# solderstation_v1_7sch.net
KiCad netlist of a schematic drawn in EAGLE
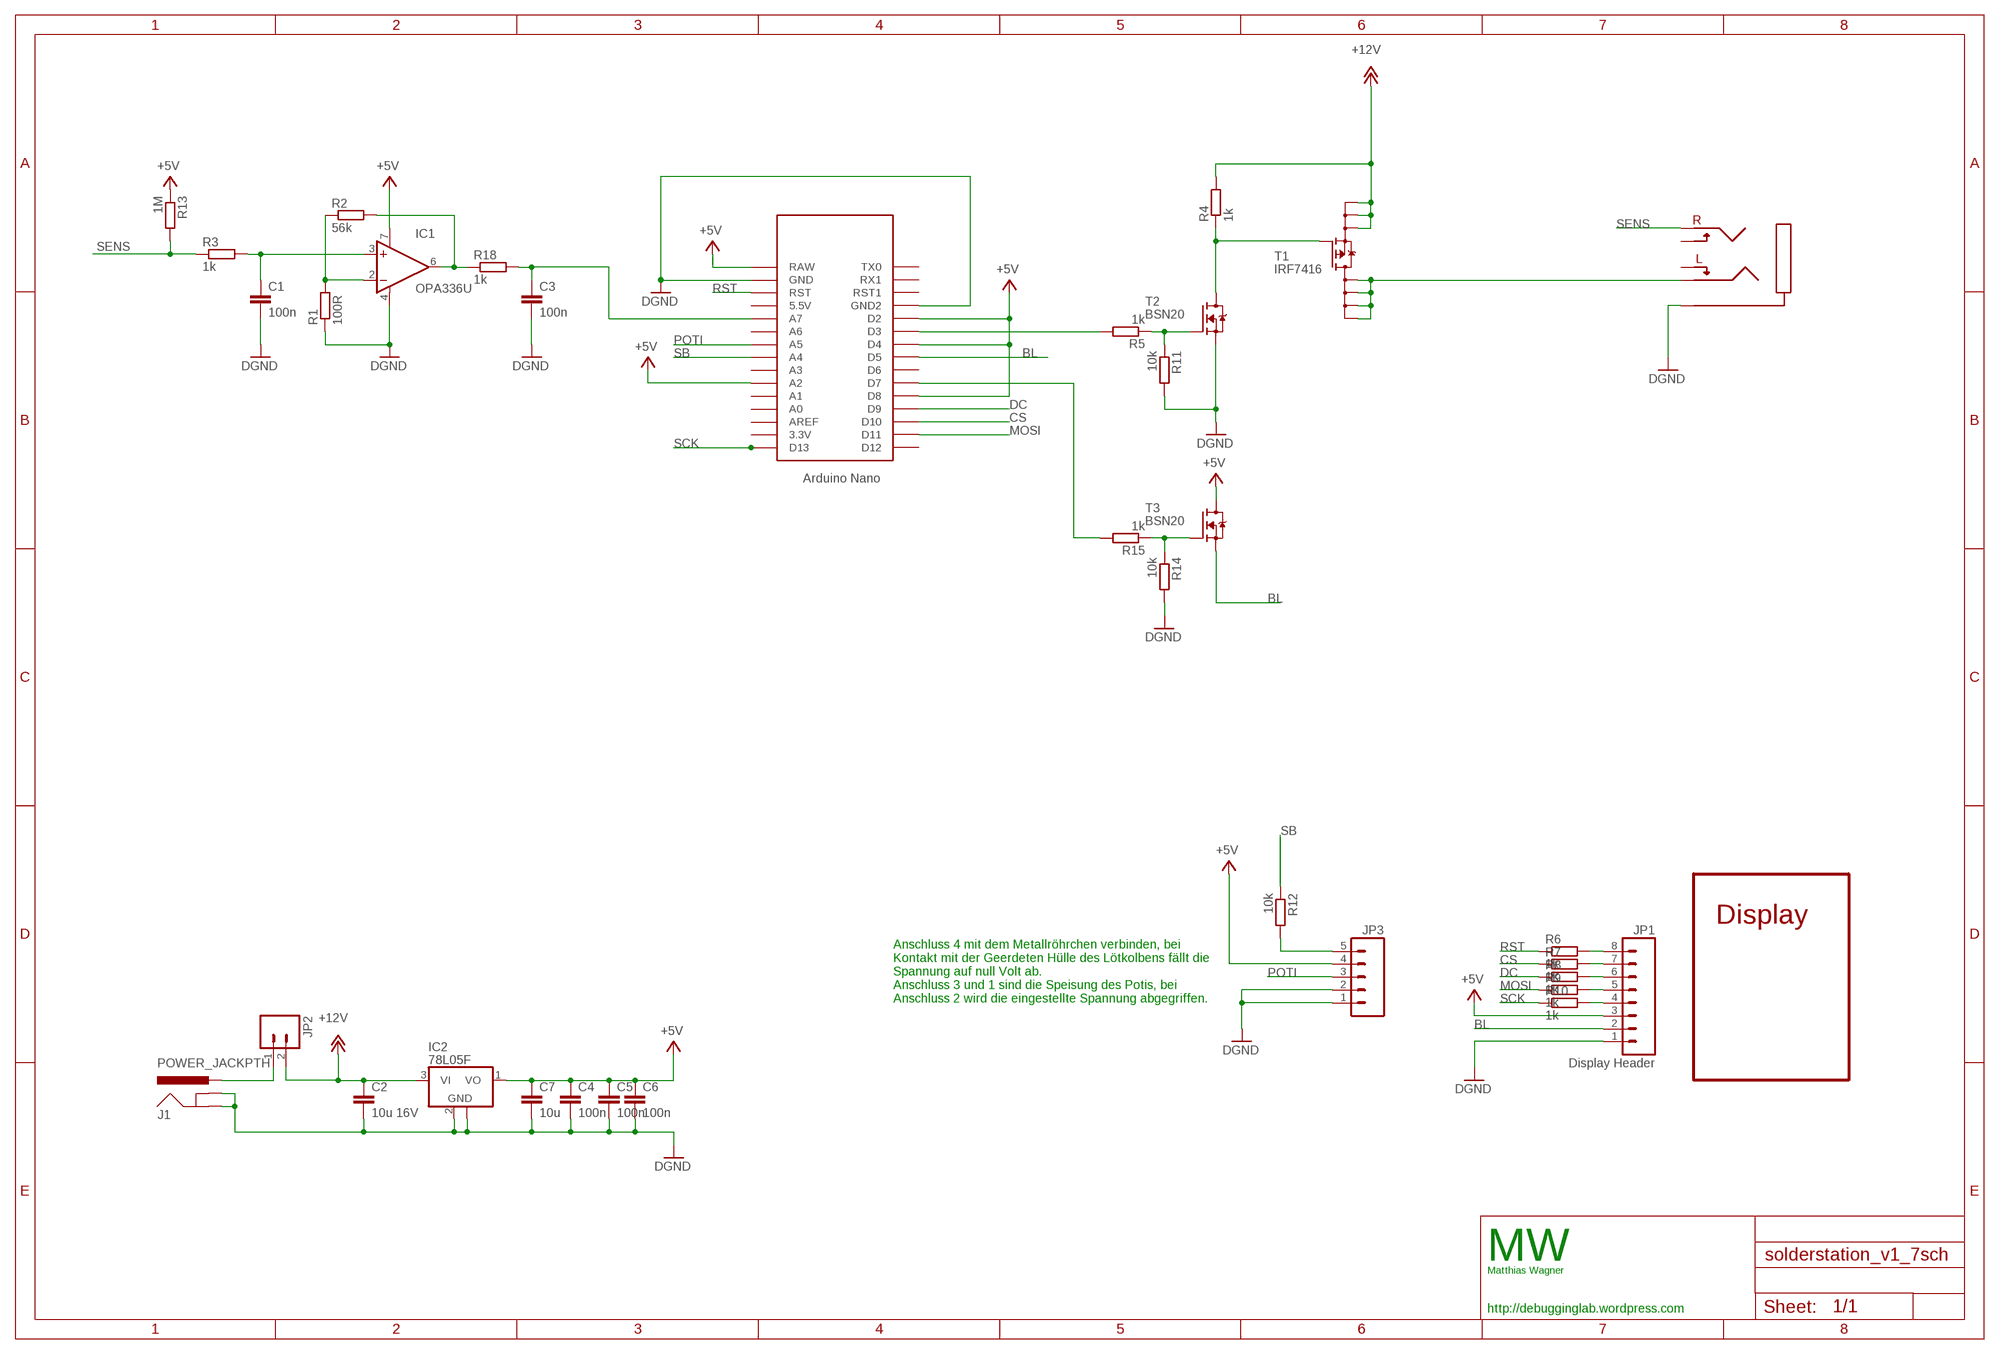
[diagram p0: schematic, sheet 1]

(export (version "E")
  (design (tool "Eeschema 10.0.6"))
  (components
    (comp (ref "C1")
      (value "100n")
      (footprint "eagle-import:C0603")
      (libsource (lib "eagle-import") (part "C-EUC0603"))
    )
    (comp (ref "C2")
      (value "10u 16V")
      (footprint "eagle-import:C1206")
      (libsource (lib "eagle-import") (part "C-EUC1206"))
    )
    (comp (ref "C3")
      (value "100n")
      (footprint "eagle-import:C0603")
      (libsource (lib "eagle-import") (part "C-EUC0603"))
    )
    (comp (ref "C4")
      (value "100n")
      (footprint "eagle-import:C0603")
      (libsource (lib "eagle-import") (part "C-EUC0603"))
    )
    (comp (ref "C5")
      (value "100n")
      (footprint "eagle-import:C0603")
      (libsource (lib "eagle-import") (part "C-EUC0603"))
    )
    (comp (ref "C6")
      (value "100n")
      (footprint "eagle-import:C0603")
      (libsource (lib "eagle-import") (part "C-EUC0603"))
    )
    (comp (ref "C7")
      (value "10u")
      (footprint "eagle-import:C1206")
      (libsource (lib "eagle-import") (part "C-EUC1206"))
    )
    (comp (ref "IC1")
      (value "OPA336U")
      (footprint "eagle-import:SO08")
      (fields (field (name "MF") "TEXAS INSTRUMENT CONNECTORS") (field (name "MPN") "OPA336UA"))
      (libsource (lib "eagle-import") (part "OPA336U"))
    )
    (comp (ref "IC2")
      (value "78L05F")
      (footprint "eagle-import:SOT89")
      (libsource (lib "eagle-import") (part "78LF05"))
    )
    (comp (ref "J1")
      (value "POWER_JACKPTH")
      (footprint "eagle-import:POWER_JACK_PTH")
      (libsource (lib "eagle-import") (part "POWER_JACKPTH"))
    )
    (comp (ref "JP1")
      (value "Display Header")
      (footprint "eagle-import:1X08_LOCK")
      (libsource (lib "eagle-import") (part "M08LOCK"))
    )
    (comp (ref "JP2")
      (value "M02LOCK_LONGPADS")
      (footprint "eagle-import:1X02_LOCK_LONGPADS")
      (libsource (lib "eagle-import") (part "M02LOCK_LONGPADS"))
    )
    (comp (ref "JP3")
      (value "M05")
      (footprint "eagle-import:05P")
      (libsource (lib "eagle-import") (part "M05"))
    )
    (comp (ref "R1")
      (value "100R")
      (footprint "eagle-import:R0603")
      (libsource (lib "eagle-import") (part "R-EU_R0603"))
    )
    (comp (ref "R2")
      (value "56k")
      (footprint "eagle-import:R0603")
      (libsource (lib "eagle-import") (part "R-EU_R0603"))
    )
    (comp (ref "R3")
      (value "1k")
      (footprint "eagle-import:R0603")
      (libsource (lib "eagle-import") (part "R-EU_R0603"))
    )
    (comp (ref "R4")
      (value "1k")
      (footprint "eagle-import:R0603")
      (libsource (lib "eagle-import") (part "R-EU_R0603"))
    )
    (comp (ref "R5")
      (value "1k")
      (footprint "eagle-import:R0603")
      (libsource (lib "eagle-import") (part "R-EU_R0603"))
    )
    (comp (ref "R6")
      (value "1k")
      (footprint "eagle-import:R0603")
      (libsource (lib "eagle-import") (part "R-EU_R0603"))
    )
    (comp (ref "R7")
      (value "1k")
      (footprint "eagle-import:R0603")
      (libsource (lib "eagle-import") (part "R-EU_R0603"))
    )
    (comp (ref "R8")
      (value "1k")
      (footprint "eagle-import:R0603")
      (libsource (lib "eagle-import") (part "R-EU_R0603"))
    )
    (comp (ref "R9")
      (value "1k")
      (footprint "eagle-import:R0603")
      (libsource (lib "eagle-import") (part "R-EU_R0603"))
    )
    (comp (ref "R10")
      (value "1k")
      (footprint "eagle-import:R0603")
      (libsource (lib "eagle-import") (part "R-EU_R0603"))
    )
    (comp (ref "R11")
      (value "10k")
      (footprint "eagle-import:R0603")
      (libsource (lib "eagle-import") (part "R-EU_R0603"))
    )
    (comp (ref "R12")
      (value "10k")
      (footprint "eagle-import:R0603")
      (libsource (lib "eagle-import") (part "R-EU_R0603"))
    )
    (comp (ref "R13")
      (value "1M")
      (footprint "eagle-import:R0603")
      (libsource (lib "eagle-import") (part "R-EU_R0603"))
    )
    (comp (ref "R14")
      (value "10k")
      (footprint "eagle-import:R0603")
      (libsource (lib "eagle-import") (part "R-EU_R0603"))
    )
    (comp (ref "R15")
      (value "1k")
      (footprint "eagle-import:R0603")
      (libsource (lib "eagle-import") (part "R-EU_R0603"))
    )
    (comp (ref "R18")
      (value "1k")
      (footprint "eagle-import:R0603")
      (libsource (lib "eagle-import") (part "R-EU_R0603"))
    )
    (comp (ref "T1")
      (value "IRF7416")
      (footprint "eagle-import:SO8")
      (libsource (lib "eagle-import") (part "IRF7416"))
    )
    (comp (ref "T2")
      (value "BSN20")
      (footprint "eagle-import:SOT23")
      (libsource (lib "eagle-import") (part "BSN20"))
    )
    (comp (ref "T3")
      (value "BSN20")
      (footprint "eagle-import:SOT23")
      (libsource (lib "eagle-import") (part "BSN20"))
    )
    (comp (ref "U$1")
      (value "NANO")
      (footprint "eagle-import:NANO")
      (libsource (lib "eagle-import") (part "NANO"))
    )
    (comp (ref "U$2")
      (value "AUDIO_JACK_3,5MMCONRAD")
      (footprint "eagle-import:AUDIO_JACK_3,5MM_CONRAD")
      (libsource (lib "eagle-import") (part "AUDIO_JACK_3,5MMCONRAD"))
    )
  )
  (nets
    (net (code "1") (name "+5V") (class "Default")
      (node (ref "C4") (pin "1") (pinfunction "1_1") (pintype "passive"))
      (node (ref "C5") (pin "1") (pinfunction "1_1") (pintype "passive"))
      (node (ref "C6") (pin "1") (pinfunction "1_1") (pintype "passive"))
      (node (ref "C7") (pin "1") (pinfunction "1_1") (pintype "passive"))
      (node (ref "IC1") (pin "7") (pinfunction "V+_7") (pintype "power_in"))
      (node (ref "IC2") (pin "1") (pinfunction "VO_1") (pintype "passive"))
      (node (ref "JP1") (pin "3") (pinfunction "3_3") (pintype "passive"))
      (node (ref "JP3") (pin "4") (pinfunction "4_4") (pintype "passive"))
      (node (ref "R13") (pin "1") (pinfunction "1_1") (pintype "passive"))
      (node (ref "T3") (pin "3") (pinfunction "D_3") (pintype "passive"))
      (node (ref "U$1") (pin "A2") (pinfunction "A2_A2") (pintype "bidirectional"))
      (node (ref "U$1") (pin "D2") (pinfunction "D2_D2") (pintype "bidirectional"))
      (node (ref "U$1") (pin "D4") (pinfunction "D4_D4") (pintype "bidirectional"))
      (node (ref "U$1") (pin "D8") (pinfunction "D8_D8") (pintype "bidirectional"))
      (node (ref "U$1") (pin "RAW") (pinfunction "RAW_RAW") (pintype "bidirectional"))
    )
    (net (code "2") (name "+12V") (class "Default")
      (node (ref "C2") (pin "1") (pinfunction "1_1") (pintype "passive"))
      (node (ref "IC2") (pin "3") (pinfunction "VI_3") (pintype "input"))
      (node (ref "JP2") (pin "2") (pinfunction "2_2") (pintype "passive"))
      (node (ref "R4") (pin "2") (pinfunction "2_2") (pintype "passive"))
      (node (ref "T1") (pin "1") (pinfunction "S0_1") (pintype "passive"))
      (node (ref "T1") (pin "2") (pinfunction "S1_2") (pintype "passive"))
      (node (ref "T1") (pin "3") (pinfunction "S2_3") (pintype "passive"))
    )
    (net (code "3") (name "/BL") (class "Default")
      (node (ref "JP1") (pin "2") (pinfunction "2_2") (pintype "passive"))
      (node (ref "T3") (pin "2") (pinfunction "S_2") (pintype "passive"))
      (node (ref "U$1") (pin "D5") (pinfunction "D5_D5") (pintype "bidirectional"))
    )
    (net (code "4") (name "/CS") (class "Default")
      (node (ref "R7") (pin "1") (pinfunction "1_1") (pintype "passive"))
      (node (ref "U$1") (pin "D10") (pinfunction "D10_D10") (pintype "bidirectional"))
    )
    (net (code "5") (name "/DC") (class "Default")
      (node (ref "R8") (pin "1") (pinfunction "1_1") (pintype "passive"))
      (node (ref "U$1") (pin "D9") (pinfunction "D9_D9") (pintype "bidirectional"))
    )
    (net (code "6") (name "/MOSI") (class "Default")
      (node (ref "R9") (pin "1") (pinfunction "1_1") (pintype "passive"))
      (node (ref "U$1") (pin "D11") (pinfunction "D11_D11") (pintype "bidirectional"))
    )
    (net (code "7") (name "/POTI") (class "Default")
      (node (ref "JP3") (pin "3") (pinfunction "3_3") (pintype "passive"))
      (node (ref "U$1") (pin "A5") (pinfunction "A5_A5") (pintype "bidirectional"))
    )
    (net (code "8") (name "/RST") (class "Default")
      (node (ref "R6") (pin "1") (pinfunction "1_1") (pintype "passive"))
      (node (ref "U$1") (pin "RST") (pinfunction "RST_RST") (pintype "bidirectional"))
    )
    (net (code "9") (name "/SB") (class "Default")
      (node (ref "R12") (pin "1") (pinfunction "1_1") (pintype "passive"))
      (node (ref "U$1") (pin "A4") (pinfunction "A4_A4") (pintype "bidirectional"))
    )
    (net (code "10") (name "/SCK") (class "Default")
      (node (ref "R10") (pin "1") (pinfunction "1_1") (pintype "passive"))
      (node (ref "U$1") (pin "D13") (pinfunction "D13_D13") (pintype "bidirectional"))
    )
    (net (code "11") (name "/SENS") (class "Default")
      (node (ref "R13") (pin "2") (pinfunction "2_2") (pintype "passive"))
      (node (ref "R3") (pin "1") (pinfunction "1_1") (pintype "passive"))
      (node (ref "U$2") (pin "P_RIGHT") (pinfunction "P$1_P_RIGHT") (pintype "bidirectional"))
    )
    (net (code "12") (name "DGND") (class "Default")
      (node (ref "C1") (pin "2") (pinfunction "2_2") (pintype "passive"))
      (node (ref "C2") (pin "2") (pinfunction "2_2") (pintype "passive"))
      (node (ref "C3") (pin "2") (pinfunction "2_2") (pintype "passive"))
      (node (ref "C4") (pin "2") (pinfunction "2_2") (pintype "passive"))
      (node (ref "C5") (pin "2") (pinfunction "2_2") (pintype "passive"))
      (node (ref "C6") (pin "2") (pinfunction "2_2") (pintype "passive"))
      (node (ref "C7") (pin "2") (pinfunction "2_2") (pintype "passive"))
      (node (ref "IC1") (pin "4") (pinfunction "V-_4") (pintype "power_in"))
      (node (ref "IC2") (pin "2") (pinfunction "GND_2") (pintype "passive"))
      (node (ref "IC2") (pin "2@1") (pinfunction "GND_2@1") (pintype "passive"))
      (node (ref "J1") (pin "GND") (pinfunction "GND_GND") (pintype "bidirectional"))
      (node (ref "J1") (pin "GNDBREAK") (pinfunction "GNDBREAK_GNDBREAK") (pintype "bidirectional"))
      (node (ref "JP1") (pin "1") (pinfunction "1_1") (pintype "passive"))
      (node (ref "JP3") (pin "1") (pinfunction "1_1") (pintype "passive"))
      (node (ref "JP3") (pin "2") (pinfunction "2_2") (pintype "passive"))
      (node (ref "R1") (pin "1") (pinfunction "1_1") (pintype "passive"))
      (node (ref "R11") (pin "2") (pinfunction "2_2") (pintype "passive"))
      (node (ref "R14") (pin "2") (pinfunction "2_2") (pintype "passive"))
      (node (ref "T2") (pin "2") (pinfunction "S_2") (pintype "passive"))
      (node (ref "U$1") (pin "GND") (pinfunction "GND_GND") (pintype "bidirectional"))
      (node (ref "U$1") (pin "GND1") (pinfunction "GND2_GND1") (pintype "bidirectional"))
      (node (ref "U$2") (pin "P_GND") (pinfunction "P$5_P_GND") (pintype "bidirectional"))
    )
    (net (code "13") (name "Net-(C3-Pad1)") (class "Default")
      (node (ref "C3") (pin "1") (pinfunction "1_1") (pintype "passive"))
      (node (ref "R18") (pin "2") (pinfunction "2_2") (pintype "passive"))
      (node (ref "U$1") (pin "A7") (pinfunction "A7_A7") (pintype "bidirectional"))
    )
    (net (code "14") (name "Net-(IC1-+IN)") (class "Default")
      (node (ref "C1") (pin "1") (pinfunction "1_1") (pintype "passive"))
      (node (ref "IC1") (pin "3") (pinfunction "+IN_3") (pintype "input"))
      (node (ref "R3") (pin "2") (pinfunction "2_2") (pintype "passive"))
    )
    (net (code "15") (name "Net-(IC1--IN)") (class "Default")
      (node (ref "IC1") (pin "2") (pinfunction "-IN_2") (pintype "input"))
      (node (ref "R1") (pin "2") (pinfunction "2_2") (pintype "passive"))
      (node (ref "R2") (pin "1") (pinfunction "1_1") (pintype "passive"))
    )
    (net (code "16") (name "Net-(IC1-OUT)") (class "Default")
      (node (ref "IC1") (pin "6") (pinfunction "OUT_6") (pintype "output"))
      (node (ref "R18") (pin "1") (pinfunction "1_1") (pintype "passive"))
      (node (ref "R2") (pin "2") (pinfunction "2_2") (pintype "passive"))
    )
    (net (code "17") (name "Net-(J1-PadPWR)") (class "Default")
      (node (ref "J1") (pin "PWR") (pinfunction "PWR_PWR") (pintype "bidirectional"))
      (node (ref "JP2") (pin "1") (pinfunction "1_1") (pintype "passive"))
    )
    (net (code "18") (name "Net-(JP1-Pad4)") (class "Default")
      (node (ref "JP1") (pin "4") (pinfunction "4_4") (pintype "passive"))
      (node (ref "R10") (pin "2") (pinfunction "2_2") (pintype "passive"))
    )
    (net (code "19") (name "Net-(JP1-Pad5)") (class "Default")
      (node (ref "JP1") (pin "5") (pinfunction "5_5") (pintype "passive"))
      (node (ref "R9") (pin "2") (pinfunction "2_2") (pintype "passive"))
    )
    (net (code "20") (name "Net-(JP1-Pad6)") (class "Default")
      (node (ref "JP1") (pin "6") (pinfunction "6_6") (pintype "passive"))
      (node (ref "R8") (pin "2") (pinfunction "2_2") (pintype "passive"))
    )
    (net (code "21") (name "Net-(JP1-Pad7)") (class "Default")
      (node (ref "JP1") (pin "7") (pinfunction "7_7") (pintype "passive"))
      (node (ref "R7") (pin "2") (pinfunction "2_2") (pintype "passive"))
    )
    (net (code "22") (name "Net-(JP1-Pad8)") (class "Default")
      (node (ref "JP1") (pin "8") (pinfunction "8_8") (pintype "passive"))
      (node (ref "R6") (pin "2") (pinfunction "2_2") (pintype "passive"))
    )
    (net (code "23") (name "Net-(JP3-Pad5)") (class "Default")
      (node (ref "JP3") (pin "5") (pinfunction "5_5") (pintype "passive"))
      (node (ref "R12") (pin "2") (pinfunction "2_2") (pintype "passive"))
    )
    (net (code "24") (name "Net-(R5-Pad2)") (class "Default")
      (node (ref "R5") (pin "2") (pinfunction "2_2") (pintype "passive"))
      (node (ref "U$1") (pin "D3") (pinfunction "D3_D3") (pintype "bidirectional"))
    )
    (net (code "25") (name "Net-(R15-Pad2)") (class "Default")
      (node (ref "R15") (pin "2") (pinfunction "2_2") (pintype "passive"))
      (node (ref "U$1") (pin "D7") (pinfunction "D7_D7") (pintype "bidirectional"))
    )
    (net (code "26") (name "Net-(T1-D0)") (class "Default")
      (node (ref "T1") (pin "5") (pinfunction "D0_5") (pintype "passive"))
      (node (ref "T1") (pin "6") (pinfunction "D1_6") (pintype "passive"))
      (node (ref "T1") (pin "7") (pinfunction "D2_7") (pintype "passive"))
      (node (ref "T1") (pin "8") (pinfunction "D3_8") (pintype "passive"))
      (node (ref "U$2") (pin "P_LEFT") (pinfunction "P$4_P_LEFT") (pintype "bidirectional"))
    )
    (net (code "27") (name "Net-(T1-G)") (class "Default")
      (node (ref "R4") (pin "1") (pinfunction "1_1") (pintype "passive"))
      (node (ref "T1") (pin "4") (pinfunction "G_4") (pintype "passive"))
      (node (ref "T2") (pin "3") (pinfunction "D_3") (pintype "passive"))
    )
    (net (code "28") (name "Net-(T2-G)") (class "Default")
      (node (ref "R11") (pin "1") (pinfunction "1_1") (pintype "passive"))
      (node (ref "R5") (pin "1") (pinfunction "1_1") (pintype "passive"))
      (node (ref "T2") (pin "1") (pinfunction "G_1") (pintype "passive"))
    )
    (net (code "29") (name "Net-(T3-G)") (class "Default")
      (node (ref "R14") (pin "1") (pinfunction "1_1") (pintype "passive"))
      (node (ref "R15") (pin "1") (pinfunction "1_1") (pintype "passive"))
      (node (ref "T3") (pin "1") (pinfunction "G_1") (pintype "passive"))
    )
    (net (code "30") (name "unconnected-(U$1-5.5V-Pad5V)") (class "Default")
      (node (ref "U$1") (pin "5V") (pinfunction "5.5V_5V") (pintype "bidirectional"))
    )
    (net (code "31") (name "unconnected-(U$1-Pad3.3V)") (class "Default")
      (node (ref "U$1") (pin "3.3V") (pinfunction "3.3V_3.3V") (pintype "bidirectional"))
    )
    (net (code "32") (name "unconnected-(U$1-PadA0)") (class "Default")
      (node (ref "U$1") (pin "A0") (pinfunction "A0_A0") (pintype "bidirectional"))
    )
    (net (code "33") (name "unconnected-(U$1-PadA1)") (class "Default")
      (node (ref "U$1") (pin "A1") (pinfunction "A1_A1") (pintype "bidirectional"))
    )
    (net (code "34") (name "unconnected-(U$1-PadA3)") (class "Default")
      (node (ref "U$1") (pin "A3") (pinfunction "A3_A3") (pintype "bidirectional"))
    )
    (net (code "35") (name "unconnected-(U$1-PadA6)") (class "Default")
      (node (ref "U$1") (pin "A6") (pinfunction "A6_A6") (pintype "bidirectional"))
    )
    (net (code "36") (name "unconnected-(U$1-PadAREF)") (class "Default")
      (node (ref "U$1") (pin "AREF") (pinfunction "AREF_AREF") (pintype "bidirectional"))
    )
    (net (code "37") (name "unconnected-(U$1-PadD6)") (class "Default")
      (node (ref "U$1") (pin "D6") (pinfunction "D6_D6") (pintype "bidirectional"))
    )
    (net (code "38") (name "unconnected-(U$1-PadD12)") (class "Default")
      (node (ref "U$1") (pin "D12") (pinfunction "D12_D12") (pintype "bidirectional"))
    )
    (net (code "39") (name "unconnected-(U$1-PadICSP1)") (class "Default")
      (node (ref "U$1") (pin "ICSP1") (pinfunction "ICSP1_ICSP1") (pintype "bidirectional"))
    )
    (net (code "40") (name "unconnected-(U$1-PadICSP2)") (class "Default")
      (node (ref "U$1") (pin "ICSP2") (pinfunction "ICSP2_ICSP2") (pintype "bidirectional"))
    )
    (net (code "41") (name "unconnected-(U$1-PadICSP3)") (class "Default")
      (node (ref "U$1") (pin "ICSP3") (pinfunction "ICSP3_ICSP3") (pintype "bidirectional"))
    )
    (net (code "42") (name "unconnected-(U$1-PadICSP4)") (class "Default")
      (node (ref "U$1") (pin "ICSP4") (pinfunction "ICSP4_ICSP4") (pintype "bidirectional"))
    )
    (net (code "43") (name "unconnected-(U$1-PadICSP5)") (class "Default")
      (node (ref "U$1") (pin "ICSP5") (pinfunction "ICSP5_ICSP5") (pintype "bidirectional"))
    )
    (net (code "44") (name "unconnected-(U$1-PadICSP6)") (class "Default")
      (node (ref "U$1") (pin "ICSP6") (pinfunction "ICSP6_ICSP6") (pintype "bidirectional"))
    )
    (net (code "45") (name "unconnected-(U$1-PadRST1)") (class "Default")
      (node (ref "U$1") (pin "RST1") (pinfunction "RST1_RST1") (pintype "bidirectional"))
    )
    (net (code "46") (name "unconnected-(U$1-PadRX1)") (class "Default")
      (node (ref "U$1") (pin "RX1") (pinfunction "RX1_RX1") (pintype "bidirectional"))
    )
    (net (code "47") (name "unconnected-(U$1-PadTX0)") (class "Default")
      (node (ref "U$1") (pin "TX0") (pinfunction "TX0_TX0") (pintype "bidirectional"))
    )
    (net (code "48") (name "unconnected-(U$2-P$2-PadP_G_R)") (class "Default")
      (node (ref "U$2") (pin "P_G_R") (pinfunction "P$2_P_G_R") (pintype "bidirectional"))
    )
    (net (code "49") (name "unconnected-(U$2-P$3-PadP_G_L)") (class "Default")
      (node (ref "U$2") (pin "P_G_L") (pinfunction "P$3_P_G_L") (pintype "bidirectional"))
    )
  )
)
